# Template2310.net
KiCad netlist of a schematic drawn in EAGLE
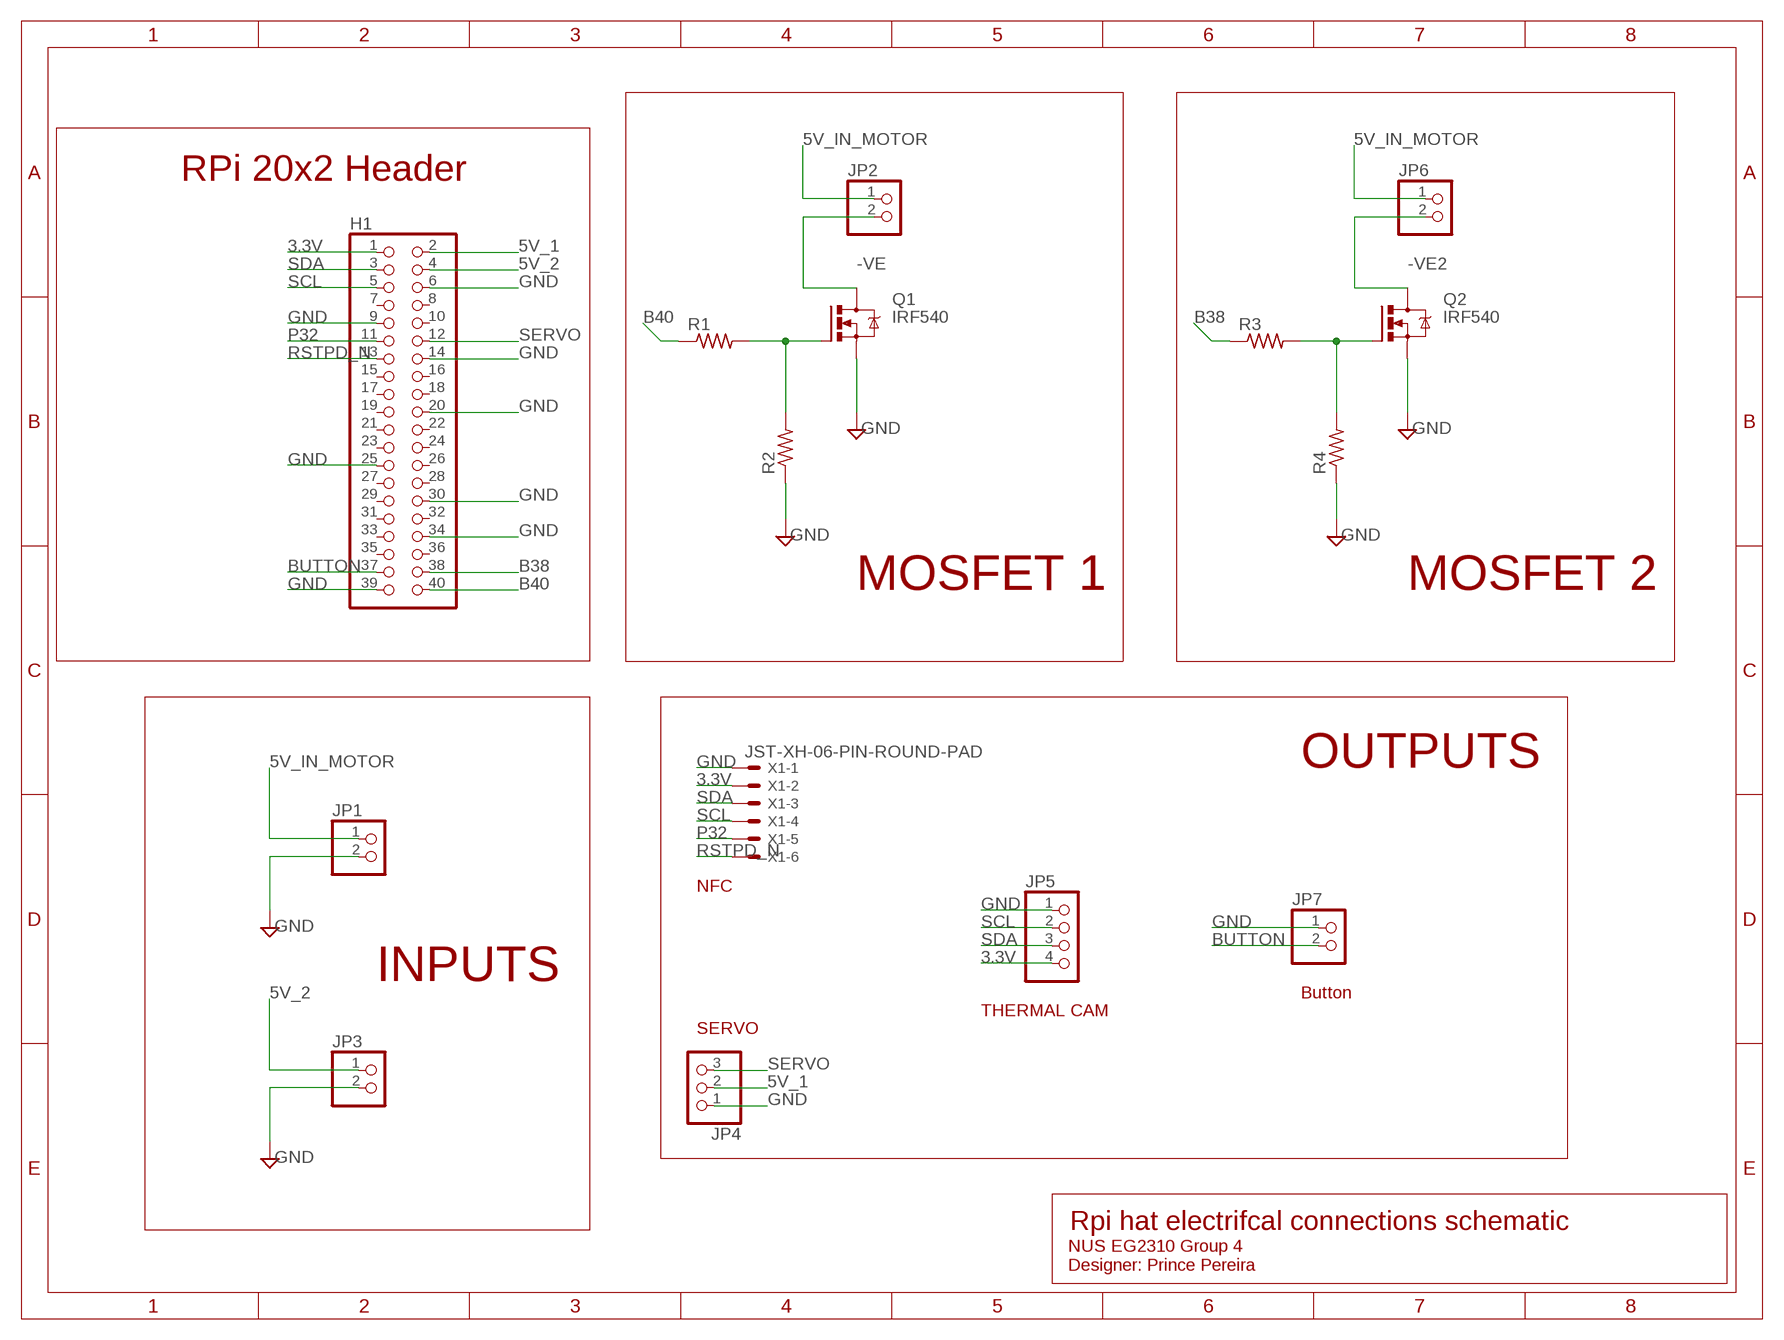
[diagram p0: schematic, sheet 1]
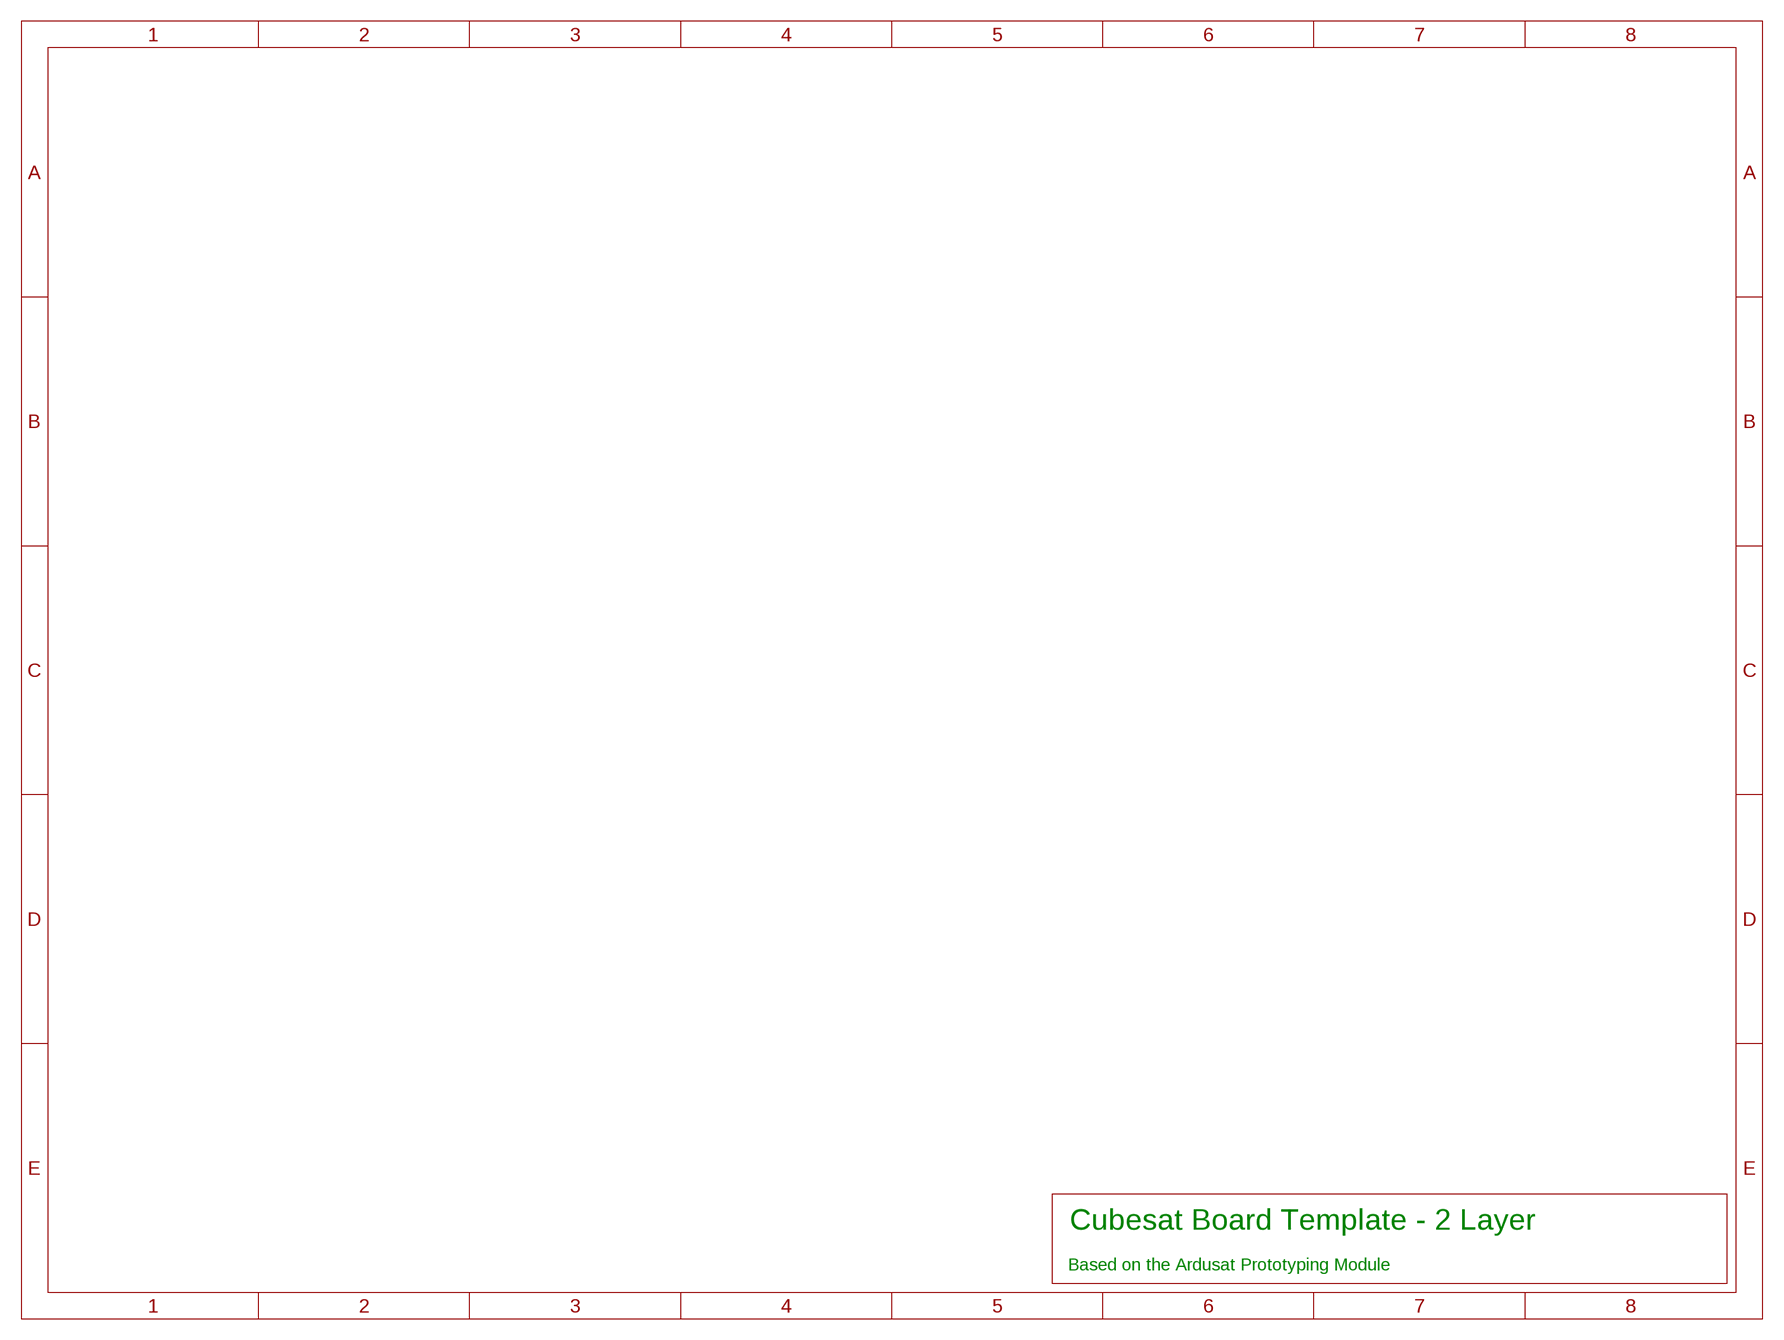
[diagram p1: schematic, sheet 2]

(export (version "E")
  (design (tool "Eeschema 10.0.6"))
  (components
    (comp (ref "H1")
      (value "PINHD-2X20")
      (footprint "eagle-import:2X20")
      (libsource (lib "eagle-import") (part "PINHD-2X20"))
    )
    (comp (ref "JP1")
      (value "PINHD-1X2")
      (footprint "eagle-import:1X02")
      (libsource (lib "eagle-import") (part "PINHD-1X2"))
    )
    (comp (ref "JP2")
      (value "PINHD-1X2")
      (footprint "eagle-import:1X02")
      (libsource (lib "eagle-import") (part "PINHD-1X2"))
    )
    (comp (ref "JP3")
      (value "PINHD-1X2")
      (footprint "eagle-import:1X02")
      (libsource (lib "eagle-import") (part "PINHD-1X2"))
    )
    (comp (ref "JP4")
      (value "PINHD-1X3/90")
      (footprint "eagle-import:1X03_90")
      (libsource (lib "eagle-import") (part "PINHD-1X3/90"))
    )
    (comp (ref "JP5")
      (value "PINHD-1X4/90")
      (footprint "eagle-import:1X04_90")
      (libsource (lib "eagle-import") (part "PINHD-1X4/90"))
    )
    (comp (ref "JP6")
      (value "PINHD-1X2")
      (footprint "eagle-import:1X02")
      (libsource (lib "eagle-import") (part "PINHD-1X2"))
    )
    (comp (ref "JP7")
      (value "PINHD-1X2/90")
      (footprint "eagle-import:1X02_90")
      (libsource (lib "eagle-import") (part "PINHD-1X2/90"))
    )
    (comp (ref "Q1")
      (value "IRF540")
      (footprint "eagle-import:TO220BV")
      (libsource (lib "eagle-import") (part "IRF540"))
    )
    (comp (ref "Q2")
      (value "IRF540")
      (footprint "eagle-import:TO220BV")
      (libsource (lib "eagle-import") (part "IRF540"))
    )
    (comp (ref "R1")
      (value "R-US_0204/7")
      (footprint "eagle-import:0204_7")
      (libsource (lib "eagle-import") (part "R-US_0204/7"))
    )
    (comp (ref "R2")
      (value "R-US_0204/7")
      (footprint "eagle-import:0204_7")
      (libsource (lib "eagle-import") (part "R-US_0204/7"))
    )
    (comp (ref "R3")
      (value "R-US_0204/7")
      (footprint "eagle-import:0204_7")
      (libsource (lib "eagle-import") (part "R-US_0204/7"))
    )
    (comp (ref "R4")
      (value "R-US_0204/7")
      (footprint "eagle-import:0204_7")
      (libsource (lib "eagle-import") (part "R-US_0204/7"))
    )
    (comp (ref "X1")
      (value "JST-XH-06-PIN-ROUND-PAD")
      (footprint "eagle-import:JST-XH-06-PACKAGE-ROUND-PAD")
      (libsource (lib "eagle-import") (part "JST-XH-06-PIN-ROUND-PAD"))
    )
  )
  (nets
    (net (code "1") (name "-VE") (class "Default")
      (node (ref "JP2") (pin "2") (pinfunction "2_2") (pintype "passive"))
      (node (ref "Q1") (pin "D") (pinfunction "D_D") (pintype "passive"))
    )
    (net (code "2") (name "-VE2") (class "Default")
      (node (ref "JP6") (pin "2") (pinfunction "2_2") (pintype "passive"))
      (node (ref "Q2") (pin "D") (pinfunction "D_D") (pintype "passive"))
    )
    (net (code "3") (name "3.3V") (class "Default")
      (node (ref "H1") (pin "1") (pinfunction "1_1") (pintype "passive"))
      (node (ref "JP5") (pin "4") (pinfunction "4_4") (pintype "passive"))
      (node (ref "X1") (pin "2") (pinfunction "S_2") (pintype "passive"))
    )
    (net (code "4") (name "5V_1") (class "Default")
      (node (ref "H1") (pin "2") (pinfunction "2_2") (pintype "passive"))
      (node (ref "JP4") (pin "2") (pinfunction "2_2") (pintype "passive"))
    )
    (net (code "5") (name "5V_2") (class "Default")
      (node (ref "H1") (pin "4") (pinfunction "4_4") (pintype "passive"))
      (node (ref "JP3") (pin "1") (pinfunction "1_1") (pintype "passive"))
    )
    (net (code "6") (name "5V_IN_MOTOR") (class "Default")
      (node (ref "JP1") (pin "1") (pinfunction "1_1") (pintype "passive"))
      (node (ref "JP2") (pin "1") (pinfunction "1_1") (pintype "passive"))
      (node (ref "JP6") (pin "1") (pinfunction "1_1") (pintype "passive"))
    )
    (net (code "7") (name "B38") (class "Default")
      (node (ref "H1") (pin "38") (pinfunction "38_38") (pintype "passive"))
      (node (ref "R3") (pin "1") (pinfunction "1_1") (pintype "passive"))
    )
    (net (code "8") (name "B40") (class "Default")
      (node (ref "H1") (pin "40") (pinfunction "40_40") (pintype "passive"))
      (node (ref "R1") (pin "1") (pinfunction "1_1") (pintype "passive"))
    )
    (net (code "9") (name "BUTTON") (class "Default")
      (node (ref "H1") (pin "37") (pinfunction "37_37") (pintype "passive"))
      (node (ref "JP7") (pin "2") (pinfunction "2_2") (pintype "passive"))
    )
    (net (code "10") (name "GND") (class "Default")
      (node (ref "H1") (pin "14") (pinfunction "14_14") (pintype "passive"))
      (node (ref "H1") (pin "20") (pinfunction "20_20") (pintype "passive"))
      (node (ref "H1") (pin "25") (pinfunction "25_25") (pintype "passive"))
      (node (ref "H1") (pin "30") (pinfunction "30_30") (pintype "passive"))
      (node (ref "H1") (pin "34") (pinfunction "34_34") (pintype "passive"))
      (node (ref "H1") (pin "39") (pinfunction "39_39") (pintype "passive"))
      (node (ref "H1") (pin "6") (pinfunction "6_6") (pintype "passive"))
      (node (ref "H1") (pin "9") (pinfunction "9_9") (pintype "passive"))
      (node (ref "JP1") (pin "2") (pinfunction "2_2") (pintype "passive"))
      (node (ref "JP3") (pin "2") (pinfunction "2_2") (pintype "passive"))
      (node (ref "JP4") (pin "1") (pinfunction "1_1") (pintype "passive"))
      (node (ref "JP5") (pin "1") (pinfunction "1_1") (pintype "passive"))
      (node (ref "JP7") (pin "1") (pinfunction "1_1") (pintype "passive"))
      (node (ref "Q1") (pin "S") (pinfunction "S_S") (pintype "passive"))
      (node (ref "Q2") (pin "S") (pinfunction "S_S") (pintype "passive"))
      (node (ref "R2") (pin "1") (pinfunction "1_1") (pintype "passive"))
      (node (ref "R4") (pin "1") (pinfunction "1_1") (pintype "passive"))
      (node (ref "X1") (pin "1") (pinfunction "S_1") (pintype "passive"))
    )
    (net (code "11") (name "Net-(Q1-PadG)") (class "Default")
      (node (ref "Q1") (pin "G") (pinfunction "G_G") (pintype "passive"))
      (node (ref "R1") (pin "2") (pinfunction "2_2") (pintype "passive"))
      (node (ref "R2") (pin "2") (pinfunction "2_2") (pintype "passive"))
    )
    (net (code "12") (name "Net-(Q2-PadG)") (class "Default")
      (node (ref "Q2") (pin "G") (pinfunction "G_G") (pintype "passive"))
      (node (ref "R3") (pin "2") (pinfunction "2_2") (pintype "passive"))
      (node (ref "R4") (pin "2") (pinfunction "2_2") (pintype "passive"))
    )
    (net (code "13") (name "P32") (class "Default")
      (node (ref "H1") (pin "11") (pinfunction "11_11") (pintype "passive"))
      (node (ref "X1") (pin "5") (pinfunction "S_5") (pintype "passive"))
    )
    (net (code "14") (name "RSTPD_N") (class "Default")
      (node (ref "H1") (pin "13") (pinfunction "13_13") (pintype "passive"))
      (node (ref "X1") (pin "6") (pinfunction "S_6") (pintype "passive"))
    )
    (net (code "15") (name "SCL") (class "Default")
      (node (ref "H1") (pin "5") (pinfunction "5_5") (pintype "passive"))
      (node (ref "JP5") (pin "2") (pinfunction "2_2") (pintype "passive"))
      (node (ref "X1") (pin "4") (pinfunction "S_4") (pintype "passive"))
    )
    (net (code "16") (name "SDA") (class "Default")
      (node (ref "H1") (pin "3") (pinfunction "3_3") (pintype "passive"))
      (node (ref "JP5") (pin "3") (pinfunction "3_3") (pintype "passive"))
      (node (ref "X1") (pin "3") (pinfunction "S_3") (pintype "passive"))
    )
    (net (code "17") (name "SERVO") (class "Default")
      (node (ref "H1") (pin "12") (pinfunction "12_12") (pintype "passive"))
      (node (ref "JP4") (pin "3") (pinfunction "3_3") (pintype "passive"))
    )
    (net (code "18") (name "unconnected-(H1-Pad7)") (class "Default")
      (node (ref "H1") (pin "7") (pinfunction "7_7") (pintype "passive"))
    )
    (net (code "19") (name "unconnected-(H1-Pad8)") (class "Default")
      (node (ref "H1") (pin "8") (pinfunction "8_8") (pintype "passive"))
    )
    (net (code "20") (name "unconnected-(H1-Pad10)") (class "Default")
      (node (ref "H1") (pin "10") (pinfunction "10_10") (pintype "passive"))
    )
    (net (code "21") (name "unconnected-(H1-Pad15)") (class "Default")
      (node (ref "H1") (pin "15") (pinfunction "15_15") (pintype "passive"))
    )
    (net (code "22") (name "unconnected-(H1-Pad16)") (class "Default")
      (node (ref "H1") (pin "16") (pinfunction "16_16") (pintype "passive"))
    )
    (net (code "23") (name "unconnected-(H1-Pad17)") (class "Default")
      (node (ref "H1") (pin "17") (pinfunction "17_17") (pintype "passive"))
    )
    (net (code "24") (name "unconnected-(H1-Pad18)") (class "Default")
      (node (ref "H1") (pin "18") (pinfunction "18_18") (pintype "passive"))
    )
    (net (code "25") (name "unconnected-(H1-Pad19)") (class "Default")
      (node (ref "H1") (pin "19") (pinfunction "19_19") (pintype "passive"))
    )
    (net (code "26") (name "unconnected-(H1-Pad21)") (class "Default")
      (node (ref "H1") (pin "21") (pinfunction "21_21") (pintype "passive"))
    )
    (net (code "27") (name "unconnected-(H1-Pad22)") (class "Default")
      (node (ref "H1") (pin "22") (pinfunction "22_22") (pintype "passive"))
    )
    (net (code "28") (name "unconnected-(H1-Pad23)") (class "Default")
      (node (ref "H1") (pin "23") (pinfunction "23_23") (pintype "passive"))
    )
    (net (code "29") (name "unconnected-(H1-Pad24)") (class "Default")
      (node (ref "H1") (pin "24") (pinfunction "24_24") (pintype "passive"))
    )
    (net (code "30") (name "unconnected-(H1-Pad26)") (class "Default")
      (node (ref "H1") (pin "26") (pinfunction "26_26") (pintype "passive"))
    )
    (net (code "31") (name "unconnected-(H1-Pad27)") (class "Default")
      (node (ref "H1") (pin "27") (pinfunction "27_27") (pintype "passive"))
    )
    (net (code "32") (name "unconnected-(H1-Pad28)") (class "Default")
      (node (ref "H1") (pin "28") (pinfunction "28_28") (pintype "passive"))
    )
    (net (code "33") (name "unconnected-(H1-Pad29)") (class "Default")
      (node (ref "H1") (pin "29") (pinfunction "29_29") (pintype "passive"))
    )
    (net (code "34") (name "unconnected-(H1-Pad31)") (class "Default")
      (node (ref "H1") (pin "31") (pinfunction "31_31") (pintype "passive"))
    )
    (net (code "35") (name "unconnected-(H1-Pad32)") (class "Default")
      (node (ref "H1") (pin "32") (pinfunction "32_32") (pintype "passive"))
    )
    (net (code "36") (name "unconnected-(H1-Pad33)") (class "Default")
      (node (ref "H1") (pin "33") (pinfunction "33_33") (pintype "passive"))
    )
    (net (code "37") (name "unconnected-(H1-Pad35)") (class "Default")
      (node (ref "H1") (pin "35") (pinfunction "35_35") (pintype "passive"))
    )
    (net (code "38") (name "unconnected-(H1-Pad36)") (class "Default")
      (node (ref "H1") (pin "36") (pinfunction "36_36") (pintype "passive"))
    )
  )
)
